# 8_digit_7_segment.net
KiCad netlist of a schematic drawn in EAGLE
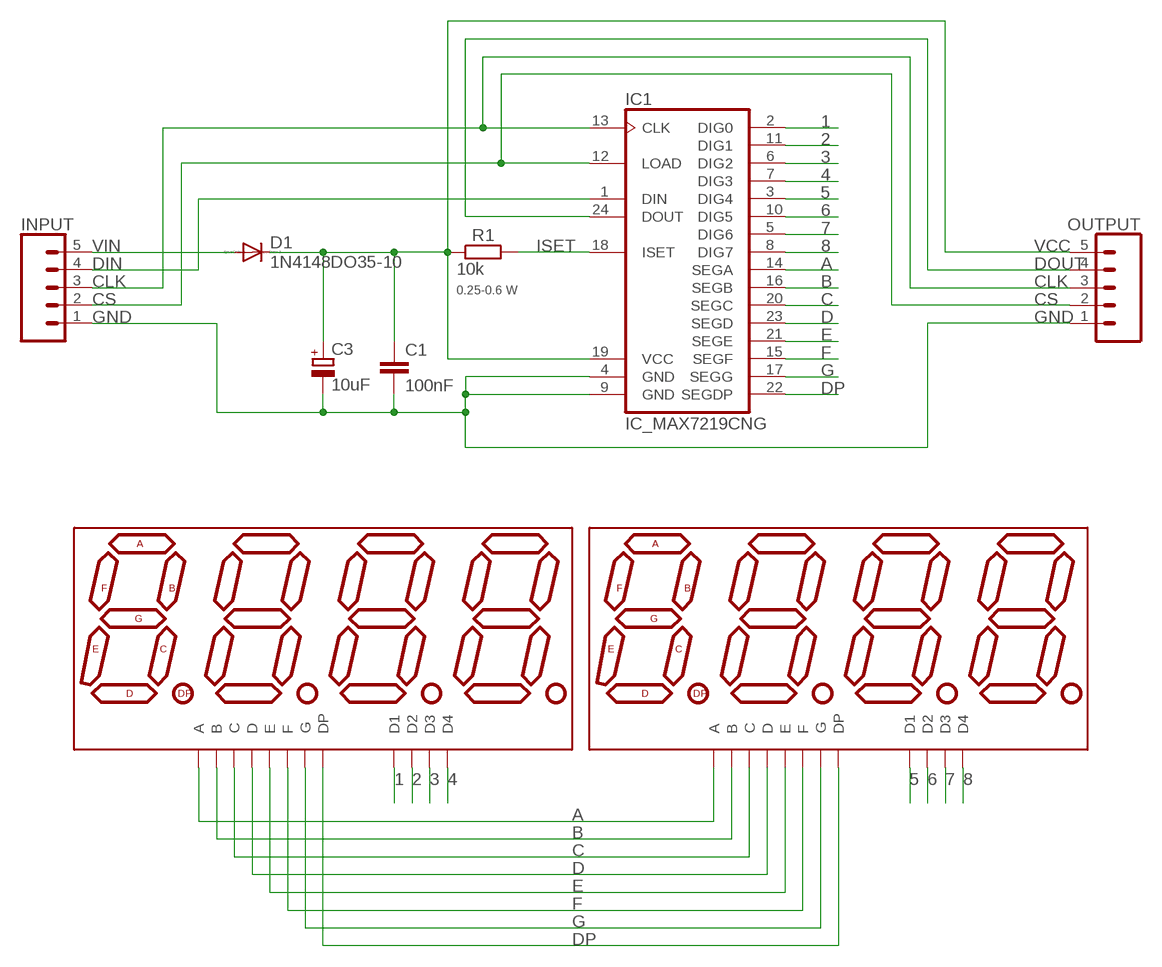
[diagram p0: schematic, sheet 1]

(export (version "E")
  (design (tool "Eeschema 10.0.6"))
  (components
    (comp (ref "C1")
      (value "100nF")
      (footprint "eagle-import:C025-024X044")
      (libsource (lib "eagle-import") (part "CAPACITOR_1025-024X044"))
    )
    (comp (ref "C3")
      (value "10uF")
      (footprint "eagle-import:E2-5")
      (libsource (lib "eagle-import") (part "CAPACITOR_POLARIZEDE2-5"))
    )
    (comp (ref "D1")
      (value "1N4148DO35-10")
      (footprint "eagle-import:D-10")
      (libsource (lib "eagle-import") (part "DIODED-10"))
    )
    (comp (ref "DISP5")
      (value "ATA8041ARBJ")
      (footprint "eagle-import:7-SEGMENT-4DIGIT-20MM")
      (libsource (lib "eagle-import") (part "DISPLAY_7_SEGMENT_4DIGIT_20MM-RED"))
    )
    (comp (ref "DISP6")
      (value "ATA8041ARBJ")
      (footprint "eagle-import:7-SEGMENT-4DIGIT-20MM")
      (libsource (lib "eagle-import") (part "DISPLAY_7_SEGMENT_4DIGIT_20MM-RED"))
    )
    (comp (ref "IC1")
      (value "IC_MAX7219CNG")
      (footprint "eagle-import:DIL24-3")
      (fields (field (name "MF") "MAXIM") (field (name "MPN") "MAX7219CNG"))
      (libsource (lib "eagle-import") (part "IC_MAX7219CNG"))
    )
    (comp (ref "INPUT")
      (value "CONN_051X05LA")
      (footprint "eagle-import:1X05_90")
      (libsource (lib "eagle-import") (part "CONN_051X05LA"))
    )
    (comp (ref "OUTPUT")
      (value "CONN_051X05/90_FEMALE")
      (footprint "eagle-import:1X05_90FEMALE")
      (libsource (lib "eagle-import") (part "CONN_051X05/90_FEMALE"))
    )
    (comp (ref "R1")
      (value "10k")
      (footprint "eagle-import:0207_7")
      (fields (field (name "POWER") "0.25-0.6 W"))
      (libsource (lib "eagle-import") (part "RESISTOR0207/7"))
    )
  )
  (nets
    (net (code "1") (name "1") (class "Default")
      (node (ref "DISP5") (pin "12") (pinfunction "D1_12") (pintype "bidirectional"))
      (node (ref "IC1") (pin "2") (pinfunction "DIG0_2") (pintype "output"))
    )
    (net (code "2") (name "2") (class "Default")
      (node (ref "DISP5") (pin "9") (pinfunction "D2_9") (pintype "bidirectional"))
      (node (ref "IC1") (pin "11") (pinfunction "DIG1_11") (pintype "output"))
    )
    (net (code "3") (name "3") (class "Default")
      (node (ref "DISP5") (pin "8") (pinfunction "D3_8") (pintype "bidirectional"))
      (node (ref "IC1") (pin "6") (pinfunction "DIG2_6") (pintype "output"))
    )
    (net (code "4") (name "4") (class "Default")
      (node (ref "DISP5") (pin "6") (pinfunction "D4_6") (pintype "bidirectional"))
      (node (ref "IC1") (pin "7") (pinfunction "DIG3_7") (pintype "output"))
    )
    (net (code "5") (name "5") (class "Default")
      (node (ref "DISP6") (pin "12") (pinfunction "D1_12") (pintype "bidirectional"))
      (node (ref "IC1") (pin "3") (pinfunction "DIG4_3") (pintype "output"))
    )
    (net (code "6") (name "6") (class "Default")
      (node (ref "DISP6") (pin "9") (pinfunction "D2_9") (pintype "bidirectional"))
      (node (ref "IC1") (pin "10") (pinfunction "DIG5_10") (pintype "output"))
    )
    (net (code "7") (name "7") (class "Default")
      (node (ref "DISP6") (pin "8") (pinfunction "D3_8") (pintype "bidirectional"))
      (node (ref "IC1") (pin "5") (pinfunction "DIG6_5") (pintype "output"))
    )
    (net (code "8") (name "8") (class "Default")
      (node (ref "DISP6") (pin "6") (pinfunction "D4_6") (pintype "bidirectional"))
      (node (ref "IC1") (pin "8") (pinfunction "DIG7_8") (pintype "output"))
    )
    (net (code "9") (name "A") (class "Default")
      (node (ref "DISP5") (pin "11") (pinfunction "A_11") (pintype "bidirectional"))
      (node (ref "DISP6") (pin "11") (pinfunction "A_11") (pintype "bidirectional"))
      (node (ref "IC1") (pin "14") (pinfunction "SEGA_14") (pintype "output"))
    )
    (net (code "10") (name "B") (class "Default")
      (node (ref "DISP5") (pin "7") (pinfunction "B_7") (pintype "bidirectional"))
      (node (ref "DISP6") (pin "7") (pinfunction "B_7") (pintype "bidirectional"))
      (node (ref "IC1") (pin "16") (pinfunction "SEGB_16") (pintype "output"))
    )
    (net (code "11") (name "C") (class "Default")
      (node (ref "DISP5") (pin "4") (pinfunction "C_4") (pintype "bidirectional"))
      (node (ref "DISP6") (pin "4") (pinfunction "C_4") (pintype "bidirectional"))
      (node (ref "IC1") (pin "20") (pinfunction "SEGC_20") (pintype "output"))
    )
    (net (code "12") (name "CLK") (class "Default")
      (node (ref "IC1") (pin "13") (pinfunction "CLK_13") (pintype "input"))
      (node (ref "INPUT") (pin "3") (pinfunction "3_3") (pintype "passive"))
      (node (ref "OUTPUT") (pin "3") (pinfunction "3_3") (pintype "passive"))
    )
    (net (code "13") (name "CS") (class "Default")
      (node (ref "IC1") (pin "12") (pinfunction "LOAD_12") (pintype "input"))
      (node (ref "INPUT") (pin "2") (pinfunction "2_2") (pintype "passive"))
      (node (ref "OUTPUT") (pin "2") (pinfunction "2_2") (pintype "passive"))
    )
    (net (code "14") (name "D") (class "Default")
      (node (ref "DISP5") (pin "2") (pinfunction "D_2") (pintype "bidirectional"))
      (node (ref "DISP6") (pin "2") (pinfunction "D_2") (pintype "bidirectional"))
      (node (ref "IC1") (pin "23") (pinfunction "SEGD_23") (pintype "output"))
    )
    (net (code "15") (name "DIN") (class "Default")
      (node (ref "IC1") (pin "1") (pinfunction "DIN_1") (pintype "input"))
      (node (ref "INPUT") (pin "4") (pinfunction "4_4") (pintype "passive"))
    )
    (net (code "16") (name "DOUT") (class "Default")
      (node (ref "IC1") (pin "24") (pinfunction "DOUT_24") (pintype "output"))
      (node (ref "OUTPUT") (pin "4") (pinfunction "4_4") (pintype "passive"))
    )
    (net (code "17") (name "DP") (class "Default")
      (node (ref "DISP5") (pin "3") (pinfunction "DP_3") (pintype "bidirectional"))
      (node (ref "DISP6") (pin "3") (pinfunction "DP_3") (pintype "bidirectional"))
      (node (ref "IC1") (pin "22") (pinfunction "SEGDP_22") (pintype "output"))
    )
    (net (code "18") (name "E") (class "Default")
      (node (ref "DISP5") (pin "1") (pinfunction "E_1") (pintype "bidirectional"))
      (node (ref "DISP6") (pin "1") (pinfunction "E_1") (pintype "bidirectional"))
      (node (ref "IC1") (pin "21") (pinfunction "SEGE_21") (pintype "output"))
    )
    (net (code "19") (name "F") (class "Default")
      (node (ref "DISP5") (pin "10") (pinfunction "F_10") (pintype "bidirectional"))
      (node (ref "DISP6") (pin "10") (pinfunction "F_10") (pintype "bidirectional"))
      (node (ref "IC1") (pin "15") (pinfunction "SEGF_15") (pintype "output"))
    )
    (net (code "20") (name "G") (class "Default")
      (node (ref "DISP5") (pin "5") (pinfunction "G_5") (pintype "bidirectional"))
      (node (ref "DISP6") (pin "5") (pinfunction "G_5") (pintype "bidirectional"))
      (node (ref "IC1") (pin "17") (pinfunction "SEGG_17") (pintype "output"))
    )
    (net (code "21") (name "GND") (class "Default")
      (node (ref "C1") (pin "2") (pinfunction "2_2") (pintype "passive"))
      (node (ref "C3") (pin "-") (pinfunction "-_-") (pintype "passive"))
      (node (ref "IC1") (pin "4") (pinfunction "GND_4") (pintype "power_in"))
      (node (ref "IC1") (pin "9") (pinfunction "GND_9") (pintype "power_in"))
      (node (ref "INPUT") (pin "1") (pinfunction "1_1") (pintype "passive"))
      (node (ref "OUTPUT") (pin "1") (pinfunction "1_1") (pintype "passive"))
    )
    (net (code "22") (name "ISET") (class "Default")
      (node (ref "IC1") (pin "18") (pinfunction "ISET_18") (pintype "input"))
      (node (ref "R1") (pin "2") (pinfunction "2_2") (pintype "passive"))
    )
    (net (code "23") (name "VCC") (class "Default")
      (node (ref "C1") (pin "1") (pinfunction "1_1") (pintype "passive"))
      (node (ref "C3") (pin "+") (pinfunction "+_+") (pintype "passive"))
      (node (ref "D1") (pin "C") (pinfunction "C_C") (pintype "passive"))
      (node (ref "IC1") (pin "19") (pinfunction "VCC_19") (pintype "power_in"))
      (node (ref "OUTPUT") (pin "5") (pinfunction "5_5") (pintype "passive"))
      (node (ref "R1") (pin "1") (pinfunction "1_1") (pintype "passive"))
    )
    (net (code "24") (name "VIN") (class "Default")
      (node (ref "D1") (pin "A") (pinfunction "A_A") (pintype "passive"))
      (node (ref "INPUT") (pin "5") (pinfunction "5_5") (pintype "passive"))
    )
  )
)
